# U_I_Meter_WIFI.net
KiCad netlist of a schematic drawn in Altium Designer
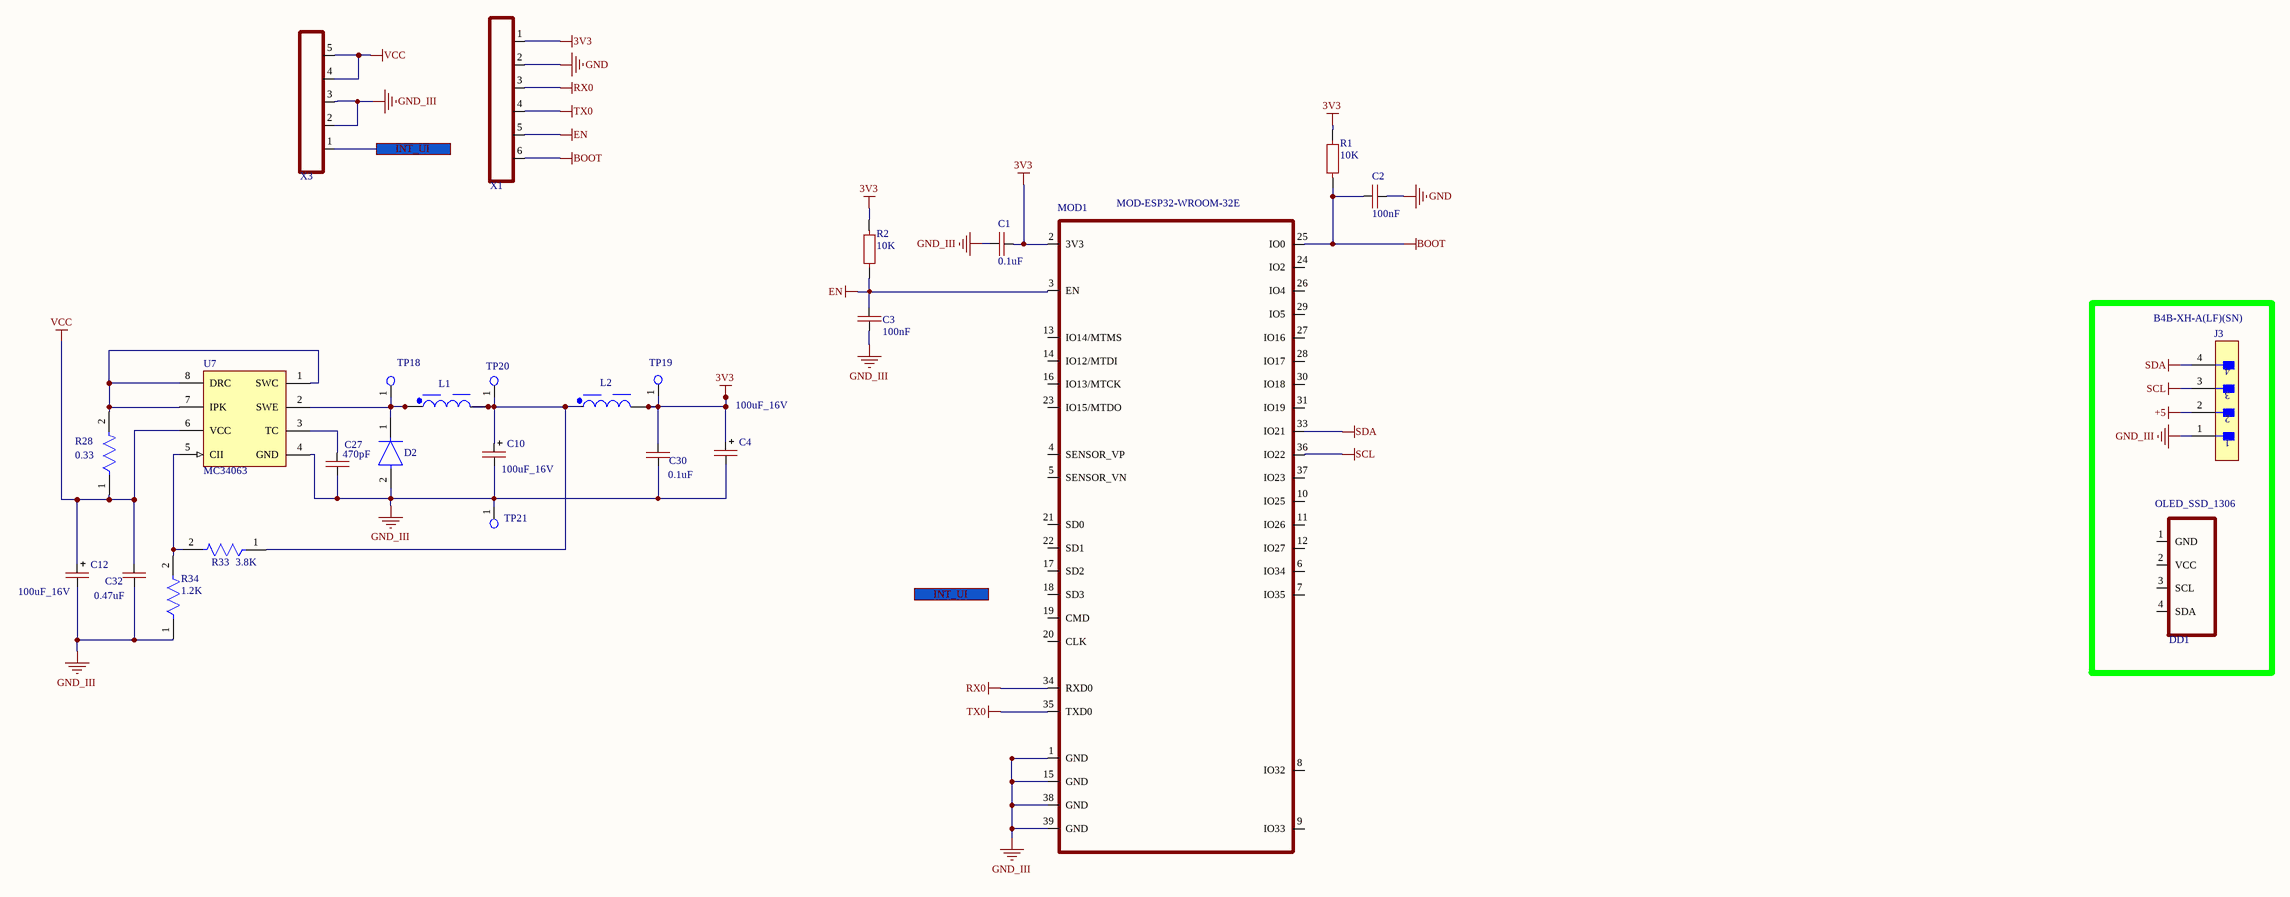
[diagram p0: U_I_Meter_WIFI.SchDoc]

(export (version "E")
  (design (tool "Eeschema 10.0.6"))
  (components
    (comp (ref "C1")
      (value "0.1uF")
      (footprint "CAP-0805")
      (libsource (lib "PASSIVE_COMPONENTS") (part "CAP-NON-POLAR"))
    )
    (comp (ref "C2")
      (value "100nF")
      (footprint "CAP-0805")
      (libsource (lib "PASSIVE_COMPONENTS") (part "CAP-NON-POLAR"))
    )
    (comp (ref "C3")
      (value "100nF")
      (footprint "CAP-0805")
      (libsource (lib "PASSIVE_COMPONENTS") (part "CAP-NON-POLAR"))
    )
    (comp (ref "C4")
      (value "100uF_16V")
      (footprint "CAP-TAN-D")
      (libsource (lib "PASSIVE_COMPONENTS") (part "CAP_POL_SMD"))
    )
    (comp (ref "C10")
      (value "100uF_16V")
      (footprint "CAP-TAN-D")
      (libsource (lib "PASSIVE_COMPONENTS") (part "CAP_POL_SMD"))
    )
    (comp (ref "C12")
      (value "100uF_16V")
      (footprint "CAP-TAN-D")
      (libsource (lib "PASSIVE_COMPONENTS") (part "CAP_POL_SMD"))
    )
    (comp (ref "C27")
      (value "470pF")
      (footprint "CAP-0805")
      (libsource (lib "PASSIVE_COMPONENTS") (part "CAP-NON-POLAR"))
    )
    (comp (ref "C30")
      (value "0.1uF")
      (footprint "CAP-0805")
      (libsource (lib "PASSIVE_COMPONENTS") (part "CAP-NON-POLAR"))
    )
    (comp (ref "C32")
      (value "0.47uF")
      (footprint "CAP-0805")
      (libsource (lib "PASSIVE_COMPONENTS") (part "CAP-NON-POLAR"))
    )
    (comp (ref "D2") (value "US1G") (footprint "US1G_SMA") (libsource (lib "Diodes") (part "US1G")))
    (comp (ref "DD1")
      (value "OLED_SSD_1306")
      (footprint "OLED_128x64_SSD_1306")
      (libsource (lib "OLED_SSD_1306") (part "OLED_SSD_1306"))
    )
    (comp (ref "J3")
      (value "B4B-XH-A(LF)(SN)")
      (footprint "B4B-XH-A")
      (libsource (lib "Connectors") (part "B4B-XH-A(LF)(SN)"))
    )
    (comp (ref "L1")
      (value "47µH, 1.17A")
      (footprint "WE-PD2_7850")
      (description "WE-PD2 SMT Power Inductor, size 7850, 47µH, 1.17A, 0.18Ω")
      (fields
        (field (name "MANUFACTURER PART NUMBER") "744775147")
        (field (name "MANUFACTURER") "Wurth Elektronik")
      )
      (libsource (lib "WE-PD2 (rev22d)") (part "744775147"))
    )
    (comp (ref "L2")
      (value "47µH, 1.17A")
      (footprint "WE-PD2_7850")
      (description "WE-PD2 SMT Power Inductor, size 7850, 47µH, 1.17A, 0.18Ω")
      (fields
        (field (name "MANUFACTURER PART NUMBER") "744775147")
        (field (name "MANUFACTURER") "Wurth Elektronik")
      )
      (libsource (lib "WE-PD2 (rev22d)") (part "744775147"))
    )
    (comp (ref "MOD1")
      (value "MOD-ESP32-WROOM-32E")
      (footprint "MOD-ESP32-WROOM-32E")
      (libsource (lib "MOD-ESP32-WROOM-32E") (part "MOD-ESP32-WROOM-32E"))
    )
    (comp (ref "R1")
      (value "10K")
      (footprint "RES-0805")
      (libsource (lib "PAS_COMPONENTS") (part "RES-CONST"))
    )
    (comp (ref "R2")
      (value "10K")
      (footprint "RES-0805")
      (libsource (lib "PAS_COMPONENTS") (part "RES-CONST"))
    )
    (comp (ref "R28")
      (value "0.33")
      (footprint "RES-1206")
      (libsource (lib "PASSIVE_COMPONENTS") (part "RES-CONST"))
    )
    (comp (ref "R33")
      (value "3.8K")
      (footprint "RES-0805")
      (description "10K")
      (libsource (lib "PASSIVE_COMPONENTS") (part "RES-CONST"))
    )
    (comp (ref "R34")
      (value "1.2K")
      (footprint "RES-0805")
      (libsource (lib "PASSIVE_COMPONENTS") (part "RES-CONST"))
    )
    (comp (ref "TP18")
      (value "Test_Point_PCB")
      (footprint "Test_Point")
      (description "Test_Point")
      (libsource (lib "Connectors") (part "TP_PCB?"))
    )
    (comp (ref "TP19")
      (value "Test_Point_PCB")
      (footprint "Test_Point")
      (description "Test_Point")
      (libsource (lib "Connectors") (part "TP_PCB?"))
    )
    (comp (ref "TP20")
      (value "Test_Point_PCB")
      (footprint "Test_Point")
      (description "Test_Point")
      (libsource (lib "Connectors") (part "TP_PCB?"))
    )
    (comp (ref "TP21")
      (value "Test_Point_PCB")
      (footprint "Pin_Test_Point(Orange)")
      (description "Test_Point")
      (libsource (lib "Connectors") (part "TP_PCB?"))
    )
    (comp (ref "U7")
      (value "MC34063")
      (footprint "SOIC-8_M")
      (libsource (lib "Integrated_Circuts") (part "MC34063"))
    )
    (comp (ref "X1")
      (value "CONN-6-PIN")
      (footprint "CONN-PLS-6-2.00mm")
      (libsource (lib "CONN_PLS") (part "CONN-6-PIN"))
    )
    (comp (ref "X3")
      (value "CONN-5-PIN")
      (footprint "CONN-PLS-5-2.54_2")
      (libsource (lib "PLS-5__") (part "CONN-5-PIN"))
    )
  )
  (nets
    (net (code "1") (name "+5") (class "Default")
      (node (ref "J3") (pin "2") (pinfunction "2_2") (pintype "passive"))
    )
    (net (code "2") (name "/INT_UI") (class "Default")
      (node (ref "X3") (pin "1") (pinfunction "1_1") (pintype "passive"))
    )
    (net (code "3") (name "3V3") (class "Default")
      (node (ref "C1") (pin "2") (pinfunction "2_2") (pintype "passive"))
      (node (ref "C30") (pin "2") (pinfunction "2_2") (pintype "passive"))
      (node (ref "C4") (pin "1") (pinfunction "+_1") (pintype "passive"))
      (node (ref "L2") (pin "2") (pinfunction "2_2") (pintype "passive"))
      (node (ref "MOD1") (pin "2") (pinfunction "3V3_2") (pintype "passive"))
      (node (ref "R1") (pin "2") (pinfunction "2_2") (pintype "passive"))
      (node (ref "R2") (pin "1") (pinfunction "1_1") (pintype "passive"))
      (node (ref "TP19") (pin "1") (pinfunction "G9_1") (pintype "passive"))
      (node (ref "X1") (pin "1") (pinfunction "1_1") (pintype "passive"))
    )
    (net (code "4") (name "BOOT") (class "Default")
      (node (ref "C2") (pin "2") (pinfunction "2_2") (pintype "passive"))
      (node (ref "MOD1") (pin "25") (pinfunction "IO0_25") (pintype "passive"))
      (node (ref "R1") (pin "1") (pinfunction "1_1") (pintype "passive"))
      (node (ref "X1") (pin "6") (pinfunction "6_6") (pintype "passive"))
    )
    (net (code "5") (name "EN") (class "Default")
      (node (ref "C3") (pin "1") (pinfunction "1_1") (pintype "passive"))
      (node (ref "MOD1") (pin "3") (pinfunction "EN_3") (pintype "passive"))
      (node (ref "R2") (pin "2") (pinfunction "2_2") (pintype "passive"))
      (node (ref "X1") (pin "5") (pinfunction "5_5") (pintype "passive"))
    )
    (net (code "6") (name "GND") (class "Default")
      (node (ref "C2") (pin "1") (pinfunction "1_1") (pintype "passive"))
      (node (ref "X1") (pin "2") (pinfunction "2_2") (pintype "passive"))
    )
    (net (code "7") (name "GND_III") (class "Default")
      (node (ref "C1") (pin "1") (pinfunction "1_1") (pintype "passive"))
      (node (ref "C10") (pin "2") (pinfunction "-_2") (pintype "passive"))
      (node (ref "C12") (pin "2") (pinfunction "-_2") (pintype "passive"))
      (node (ref "C27") (pin "2") (pinfunction "2_2") (pintype "passive"))
      (node (ref "C3") (pin "2") (pinfunction "2_2") (pintype "passive"))
      (node (ref "C30") (pin "1") (pinfunction "1_1") (pintype "passive"))
      (node (ref "C32") (pin "2") (pinfunction "2_2") (pintype "passive"))
      (node (ref "C4") (pin "2") (pinfunction "-_2") (pintype "passive"))
      (node (ref "D2") (pin "2") (pinfunction "A_2") (pintype "passive"))
      (node (ref "J3") (pin "1") (pinfunction "1_1") (pintype "passive"))
      (node (ref "MOD1") (pin "1") (pinfunction "GND_1") (pintype "passive"))
      (node (ref "MOD1") (pin "15") (pinfunction "GND_15") (pintype "passive"))
      (node (ref "MOD1") (pin "38") (pinfunction "GND_38") (pintype "passive"))
      (node (ref "MOD1") (pin "39") (pinfunction "GND_39") (pintype "passive"))
      (node (ref "R34") (pin "1") (pinfunction "1_1") (pintype "passive"))
      (node (ref "TP21") (pin "1") (pinfunction "G9_1") (pintype "passive"))
      (node (ref "U7") (pin "4") (pinfunction "GND_4") (pintype "power_in"))
      (node (ref "X3") (pin "2") (pinfunction "2_2") (pintype "passive"))
      (node (ref "X3") (pin "3") (pinfunction "3_3") (pintype "passive"))
    )
    (net (code "8") (name "Net-(C10-+)") (class "Default")
      (node (ref "C10") (pin "1") (pinfunction "+_1") (pintype "passive"))
      (node (ref "L1") (pin "2") (pinfunction "2_2") (pintype "passive"))
      (node (ref "L2") (pin "1") (pinfunction "1_1") (pintype "passive"))
      (node (ref "R33") (pin "1") (pinfunction "1_1") (pintype "passive"))
      (node (ref "TP20") (pin "1") (pinfunction "G9_1") (pintype "passive"))
    )
    (net (code "9") (name "Net-(D2-C)") (class "Default")
      (node (ref "D2") (pin "1") (pinfunction "C_1") (pintype "passive"))
      (node (ref "L1") (pin "1") (pinfunction "1_1") (pintype "passive"))
      (node (ref "TP18") (pin "1") (pinfunction "G9_1") (pintype "passive"))
      (node (ref "U7") (pin "2") (pinfunction "SWE_2") (pintype "open_emitter"))
    )
    (net (code "10") (name "Net-(U7-CII)") (class "Default")
      (node (ref "R33") (pin "2") (pinfunction "2_2") (pintype "passive"))
      (node (ref "R34") (pin "2") (pinfunction "2_2") (pintype "passive"))
      (node (ref "U7") (pin "5") (pinfunction "CII_5") (pintype "input"))
    )
    (net (code "11") (name "Net-(U7-DRC)") (class "Default")
      (node (ref "R28") (pin "2") (pinfunction "2_2") (pintype "passive"))
      (node (ref "U7") (pin "1") (pinfunction "SWC_1") (pintype "open_collector"))
      (node (ref "U7") (pin "7") (pinfunction "IPK_7") (pintype "passive"))
      (node (ref "U7") (pin "8") (pinfunction "DRC_8") (pintype "open_collector"))
    )
    (net (code "12") (name "Net-(U7-TC)") (class "Default")
      (node (ref "C27") (pin "1") (pinfunction "1_1") (pintype "passive"))
      (node (ref "U7") (pin "3") (pinfunction "TC_3") (pintype "passive"))
    )
    (net (code "13") (name "RX0") (class "Default")
      (node (ref "MOD1") (pin "34") (pinfunction "RXD0_34") (pintype "passive"))
      (node (ref "X1") (pin "3") (pinfunction "3_3") (pintype "passive"))
    )
    (net (code "14") (name "SCL") (class "Default")
      (node (ref "J3") (pin "3") (pinfunction "3_3") (pintype "passive"))
      (node (ref "MOD1") (pin "36") (pinfunction "IO22_36") (pintype "passive"))
    )
    (net (code "15") (name "SDA") (class "Default")
      (node (ref "J3") (pin "4") (pinfunction "4_4") (pintype "passive"))
      (node (ref "MOD1") (pin "33") (pinfunction "IO21_33") (pintype "passive"))
    )
    (net (code "16") (name "TX0") (class "Default")
      (node (ref "MOD1") (pin "35") (pinfunction "TXD0_35") (pintype "passive"))
      (node (ref "X1") (pin "4") (pinfunction "4_4") (pintype "passive"))
    )
    (net (code "17") (name "VCC") (class "Default")
      (node (ref "C12") (pin "1") (pinfunction "+_1") (pintype "passive"))
      (node (ref "C32") (pin "1") (pinfunction "1_1") (pintype "passive"))
      (node (ref "R28") (pin "1") (pinfunction "1_1") (pintype "passive"))
      (node (ref "U7") (pin "6") (pinfunction "VCC_6") (pintype "power_in"))
      (node (ref "X3") (pin "4") (pinfunction "4_4") (pintype "passive"))
      (node (ref "X3") (pin "5") (pinfunction "5_5") (pintype "passive"))
    )
    (net (code "18") (name "unconnected-(DD1-GND-Pad1)") (class "Default")
      (node (ref "DD1") (pin "1") (pinfunction "GND_1") (pintype "passive"))
    )
    (net (code "19") (name "unconnected-(DD1-SCL-Pad3)") (class "Default")
      (node (ref "DD1") (pin "3") (pinfunction "SCL_3") (pintype "passive"))
    )
    (net (code "20") (name "unconnected-(DD1-SDA-Pad4)") (class "Default")
      (node (ref "DD1") (pin "4") (pinfunction "SDA_4") (pintype "passive"))
    )
    (net (code "21") (name "unconnected-(DD1-VCC-Pad2)") (class "Default")
      (node (ref "DD1") (pin "2") (pinfunction "VCC_2") (pintype "passive"))
    )
    (net (code "22") (name "unconnected-(MOD1-CLK-Pad20)") (class "Default")
      (node (ref "MOD1") (pin "20") (pinfunction "CLK_20") (pintype "passive"))
    )
    (net (code "23") (name "unconnected-(MOD1-CMD-Pad19)") (class "Default")
      (node (ref "MOD1") (pin "19") (pinfunction "CMD_19") (pintype "passive"))
    )
    (net (code "24") (name "unconnected-(MOD1-IO2-Pad24)") (class "Default")
      (node (ref "MOD1") (pin "24") (pinfunction "IO2_24") (pintype "passive"))
    )
    (net (code "25") (name "unconnected-(MOD1-IO4-Pad26)") (class "Default")
      (node (ref "MOD1") (pin "26") (pinfunction "IO4_26") (pintype "passive"))
    )
    (net (code "26") (name "unconnected-(MOD1-IO5-Pad29)") (class "Default")
      (node (ref "MOD1") (pin "29") (pinfunction "IO5_29") (pintype "passive"))
    )
    (net (code "27") (name "unconnected-(MOD1-IO12{slash}MTDI-Pad14)") (class "Default")
      (node (ref "MOD1") (pin "14") (pinfunction "IO12/MTDI_14") (pintype "passive"))
    )
    (net (code "28") (name "unconnected-(MOD1-IO13{slash}MTCK-Pad16)") (class "Default")
      (node (ref "MOD1") (pin "16") (pinfunction "IO13/MTCK_16") (pintype "passive"))
    )
    (net (code "29") (name "unconnected-(MOD1-IO14{slash}MTMS-Pad13)") (class "Default")
      (node (ref "MOD1") (pin "13") (pinfunction "IO14/MTMS_13") (pintype "passive"))
    )
    (net (code "30") (name "unconnected-(MOD1-IO15{slash}MTDO-Pad23)") (class "Default")
      (node (ref "MOD1") (pin "23") (pinfunction "IO15/MTDO_23") (pintype "passive"))
    )
    (net (code "31") (name "unconnected-(MOD1-IO16-Pad27)") (class "Default")
      (node (ref "MOD1") (pin "27") (pinfunction "IO16_27") (pintype "passive"))
    )
    (net (code "32") (name "unconnected-(MOD1-IO17-Pad28)") (class "Default")
      (node (ref "MOD1") (pin "28") (pinfunction "IO17_28") (pintype "passive"))
    )
    (net (code "33") (name "unconnected-(MOD1-IO18-Pad30)") (class "Default")
      (node (ref "MOD1") (pin "30") (pinfunction "IO18_30") (pintype "passive"))
    )
    (net (code "34") (name "unconnected-(MOD1-IO19-Pad31)") (class "Default")
      (node (ref "MOD1") (pin "31") (pinfunction "IO19_31") (pintype "passive"))
    )
    (net (code "35") (name "unconnected-(MOD1-IO23-Pad37)") (class "Default")
      (node (ref "MOD1") (pin "37") (pinfunction "IO23_37") (pintype "passive"))
    )
    (net (code "36") (name "unconnected-(MOD1-IO25-Pad10)") (class "Default")
      (node (ref "MOD1") (pin "10") (pinfunction "IO25_10") (pintype "passive"))
    )
    (net (code "37") (name "unconnected-(MOD1-IO26-Pad11)") (class "Default")
      (node (ref "MOD1") (pin "11") (pinfunction "IO26_11") (pintype "passive"))
    )
    (net (code "38") (name "unconnected-(MOD1-IO27-Pad12)") (class "Default")
      (node (ref "MOD1") (pin "12") (pinfunction "IO27_12") (pintype "passive"))
    )
    (net (code "39") (name "unconnected-(MOD1-IO32-Pad8)") (class "Default")
      (node (ref "MOD1") (pin "8") (pinfunction "IO32_8") (pintype "passive"))
    )
    (net (code "40") (name "unconnected-(MOD1-IO33-Pad9)") (class "Default")
      (node (ref "MOD1") (pin "9") (pinfunction "IO33_9") (pintype "passive"))
    )
    (net (code "41") (name "unconnected-(MOD1-IO34-Pad6)") (class "Default")
      (node (ref "MOD1") (pin "6") (pinfunction "IO34_6") (pintype "passive"))
    )
    (net (code "42") (name "unconnected-(MOD1-IO35-Pad7)") (class "Default")
      (node (ref "MOD1") (pin "7") (pinfunction "IO35_7") (pintype "passive"))
    )
    (net (code "43") (name "unconnected-(MOD1-SD0-Pad21)") (class "Default")
      (node (ref "MOD1") (pin "21") (pinfunction "SD0_21") (pintype "passive"))
    )
    (net (code "44") (name "unconnected-(MOD1-SD1-Pad22)") (class "Default")
      (node (ref "MOD1") (pin "22") (pinfunction "SD1_22") (pintype "passive"))
    )
    (net (code "45") (name "unconnected-(MOD1-SD2-Pad17)") (class "Default")
      (node (ref "MOD1") (pin "17") (pinfunction "SD2_17") (pintype "passive"))
    )
    (net (code "46") (name "unconnected-(MOD1-SD3-Pad18)") (class "Default")
      (node (ref "MOD1") (pin "18") (pinfunction "SD3_18") (pintype "passive"))
    )
    (net (code "47") (name "unconnected-(MOD1-SENSOR_VN-Pad5)") (class "Default")
      (node (ref "MOD1") (pin "5") (pinfunction "SENSOR_VN_5") (pintype "passive"))
    )
    (net (code "48") (name "unconnected-(MOD1-SENSOR_VP-Pad4)") (class "Default")
      (node (ref "MOD1") (pin "4") (pinfunction "SENSOR_VP_4") (pintype "passive"))
    )
  )
)
